# v0_4_0.net
KiCad netlist of a schematic drawn in EAGLE
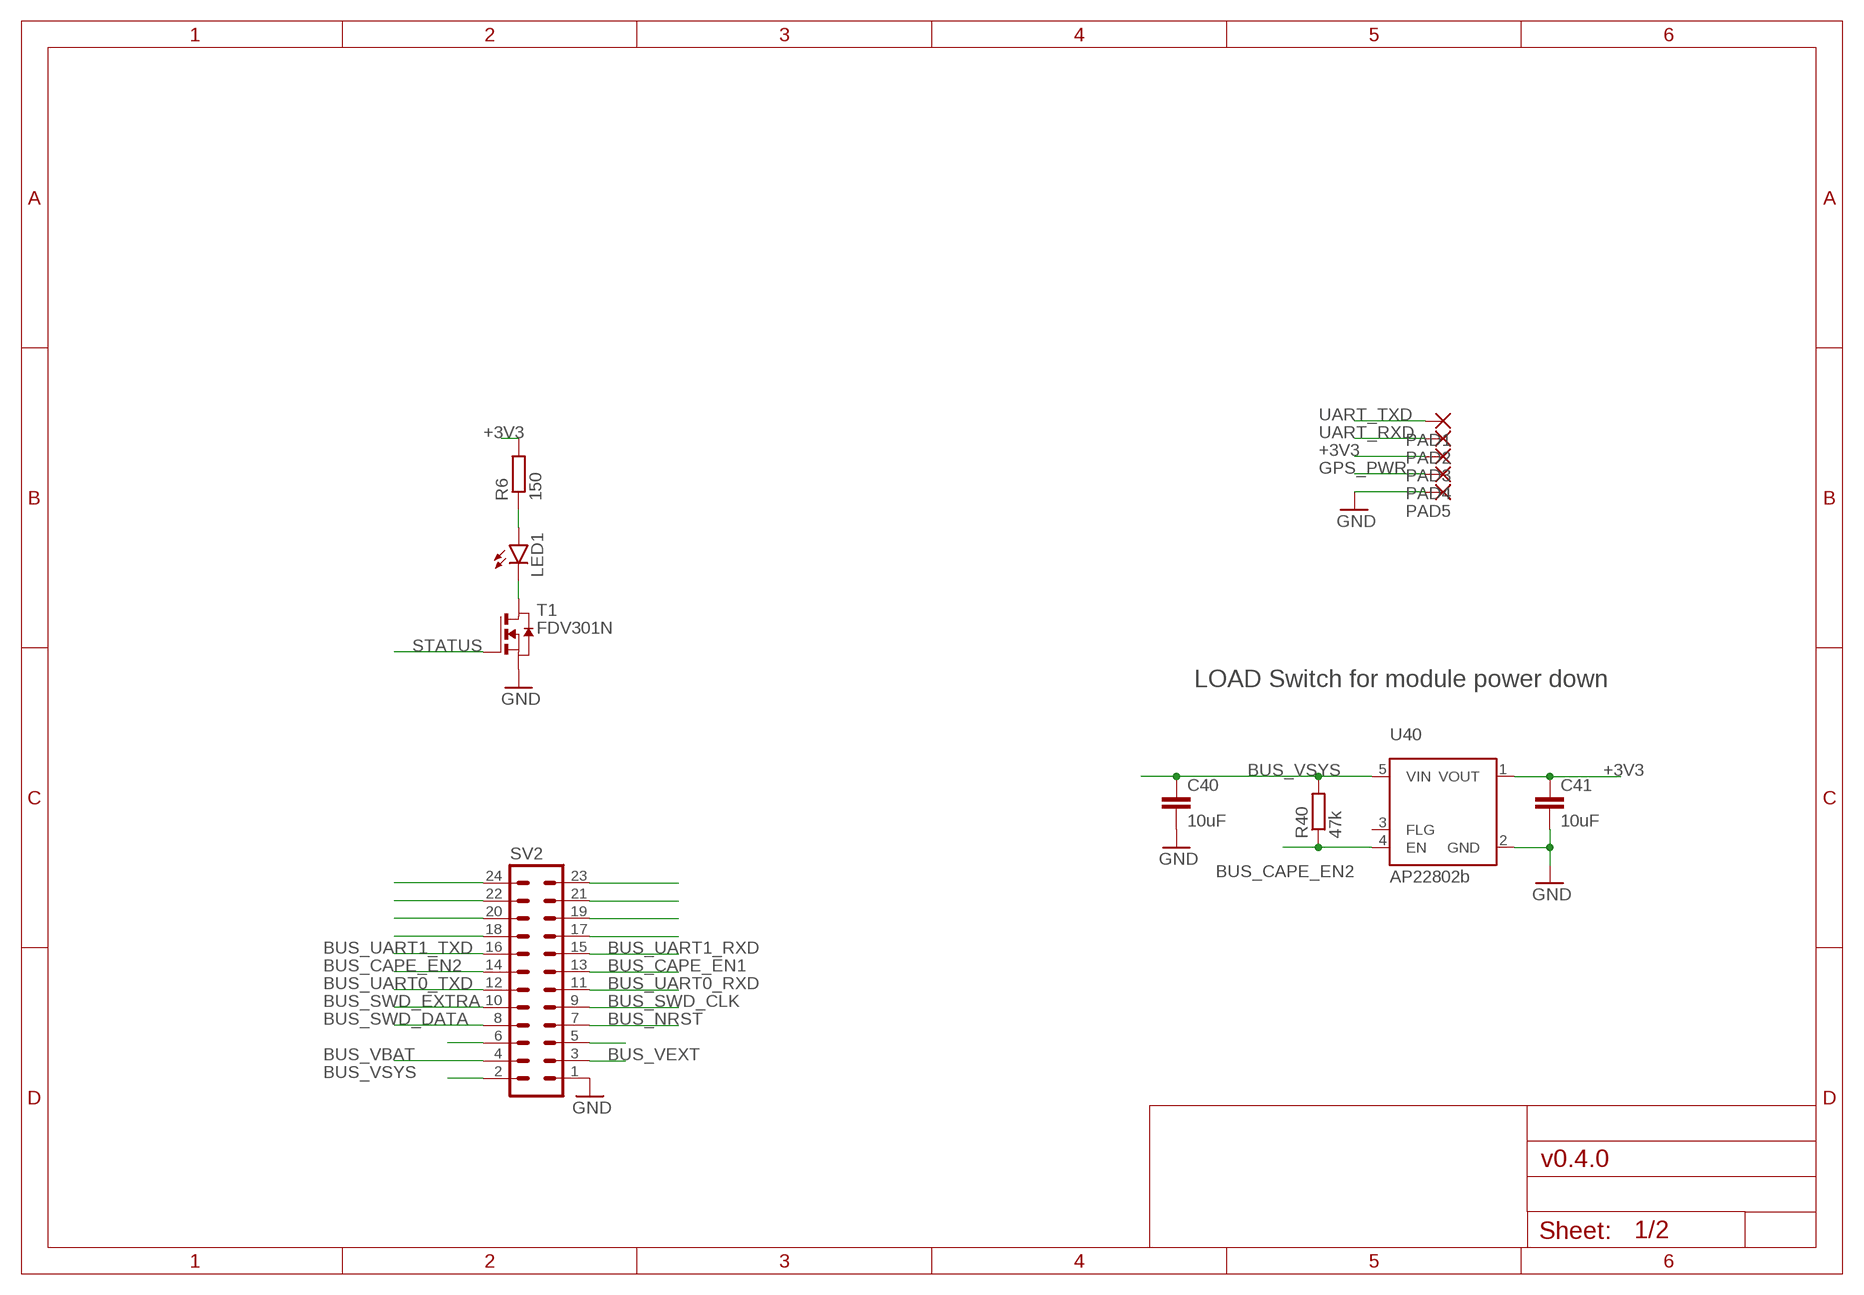
[diagram p0: schematic, sheet 1]
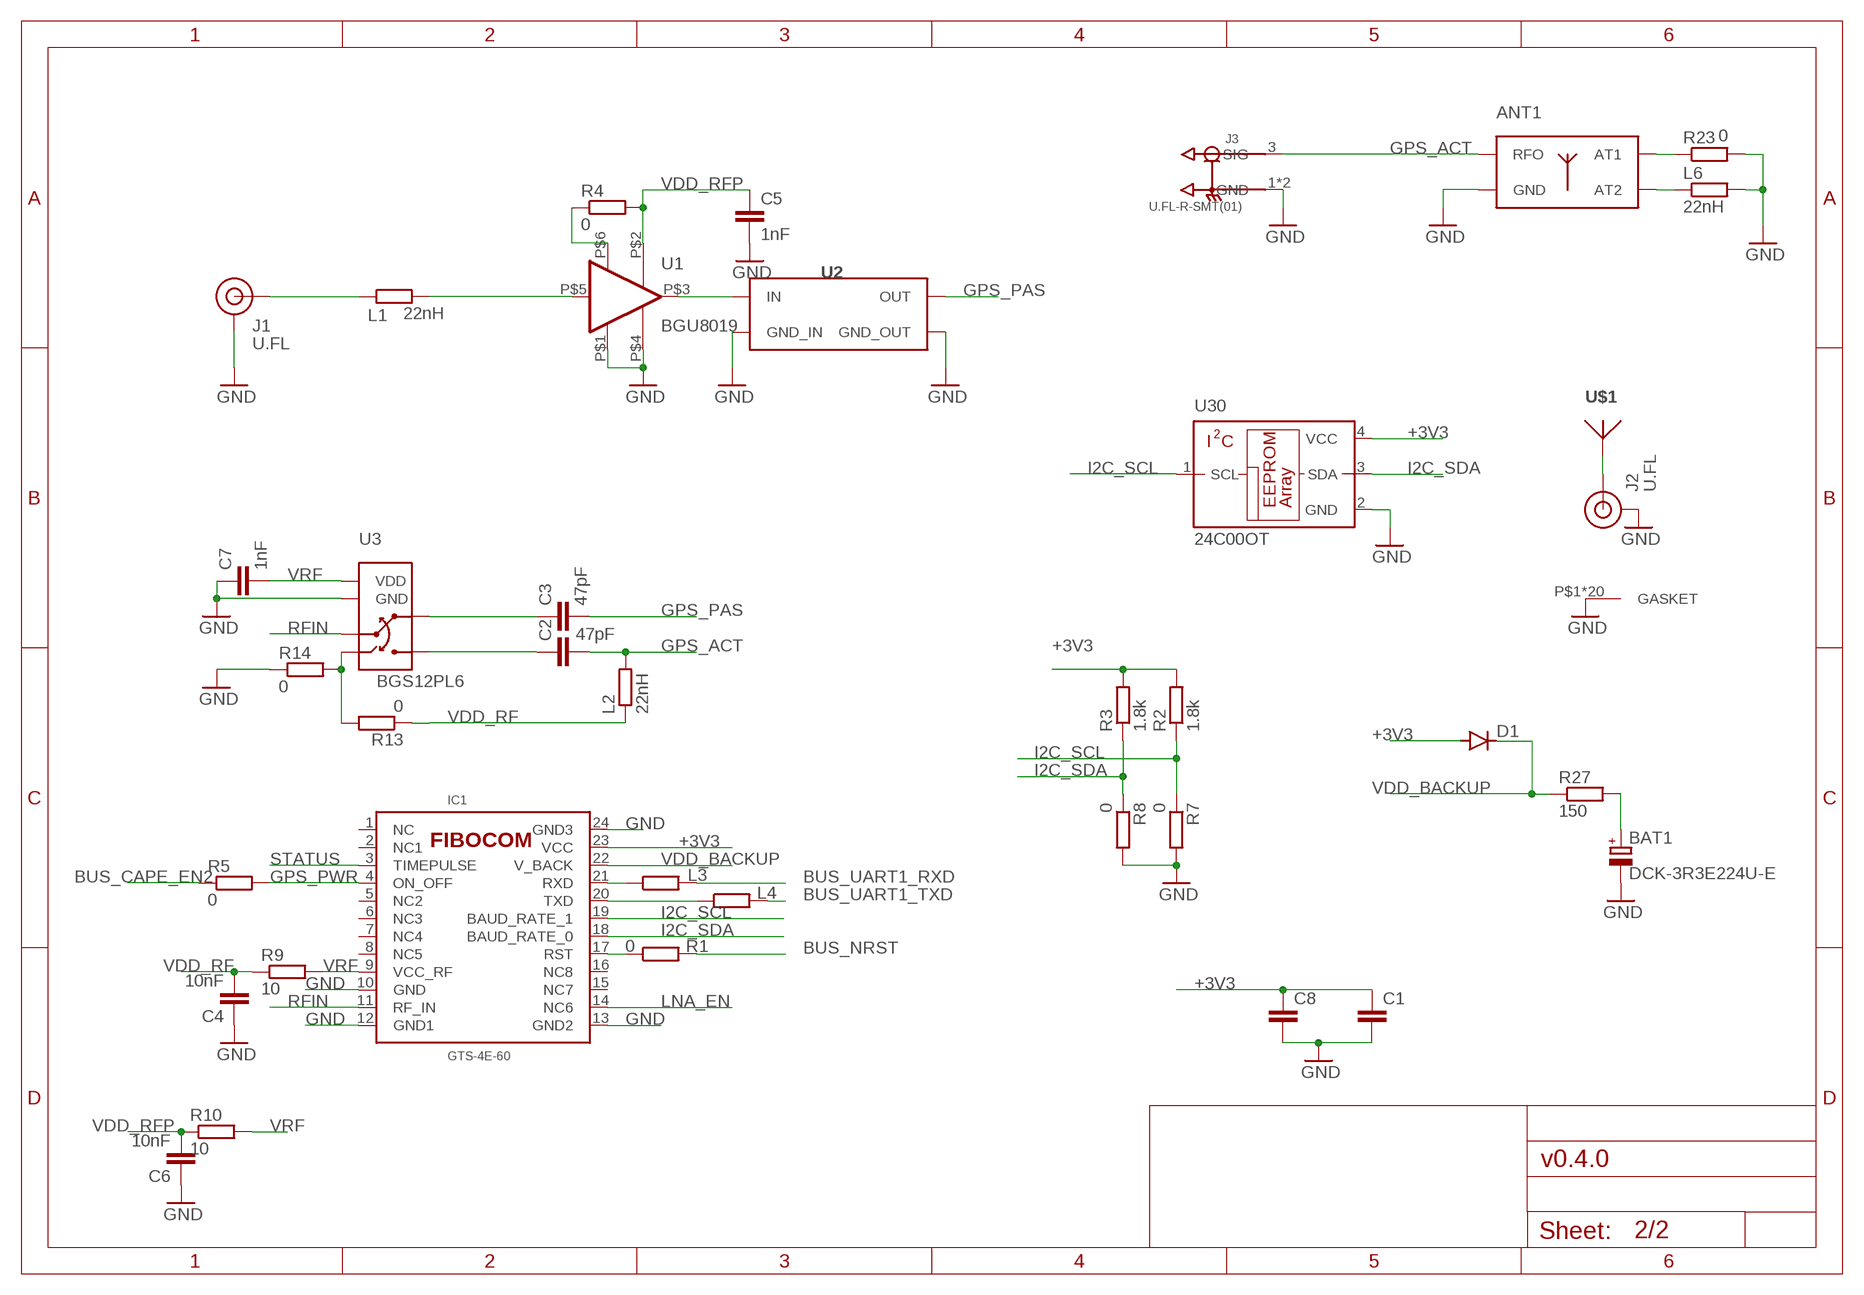
[diagram p1: schematic, sheet 2]

(export (version "E")
  (design (tool "Eeschema 10.0.6"))
  (components
    (comp (ref "ANT1")
      (value "M20047")
      (footprint "eagle-import:PCBCOMPONENT_1")
      (libsource (lib "eagle-import") (part "M20047"))
    )
    (comp (ref "BAT1")
      (value "DCK-3R3E224U-E")
      (footprint "eagle-import:621")
      (libsource (lib "eagle-import") (part "DCK-3R3E224U-E"))
    )
    (comp (ref "C1")
      (value "C-EUC0603")
      (footprint "eagle-import:C0603")
      (libsource (lib "eagle-import") (part "C-EUC0603"))
    )
    (comp (ref "C2")
      (value "47pF")
      (footprint "eagle-import:C0402")
      (libsource (lib "eagle-import") (part "C-EUC0402"))
    )
    (comp (ref "C3")
      (value "47pF")
      (footprint "eagle-import:C0402")
      (libsource (lib "eagle-import") (part "C-EUC0402"))
    )
    (comp (ref "C4")
      (value "10nF")
      (footprint "eagle-import:C0402")
      (libsource (lib "eagle-import") (part "C-EUC0402"))
    )
    (comp (ref "C5")
      (value "1nF")
      (footprint "eagle-import:C0402")
      (libsource (lib "eagle-import") (part "C-EUC0402"))
    )
    (comp (ref "C6")
      (value "10nF")
      (footprint "eagle-import:C0402")
      (libsource (lib "eagle-import") (part "C-EUC0402"))
    )
    (comp (ref "C7")
      (value "1nF")
      (footprint "eagle-import:C0402")
      (libsource (lib "eagle-import") (part "C-EUC0402"))
    )
    (comp (ref "C8")
      (value "C-EUC0402")
      (footprint "eagle-import:C0402")
      (libsource (lib "eagle-import") (part "C-EUC0402"))
    )
    (comp (ref "D1")
      (value "DIODE-SOD323-R")
      (footprint "eagle-import:SOD323-R")
      (libsource (lib "eagle-import") (part "DIODE-SOD323-R"))
    )
    (comp (ref "IC1")
      (value "GTS-4E-60")
      (footprint "eagle-import:_GTS_4E_60")
      (libsource (lib "eagle-import") (part "GTS-4E-60"))
    )
    (comp (ref "J1")
      (value "U.FL")
      (footprint "eagle-import:U.FL")
      (libsource (lib "eagle-import") (part "U.FL2PIN"))
    )
    (comp (ref "J2")
      (value "U.FL")
      (footprint "eagle-import:U.FL")
      (libsource (lib "eagle-import") (part "U.FL2PIN"))
    )
    (comp (ref "J3")
      (value "U.FL-R-SMT(01)")
      (footprint "eagle-import:HRS_U.FL-R-SMT(01)")
      (fields (field (name "MF") "Hirose") (field (name "MP") "U.FL-R-SMT_01_"))
      (libsource (lib "eagle-import") (part "U.FL-R-SMT(01)"))
    )
    (comp (ref "L1")
      (value "22nH")
      (footprint "eagle-import:R0402")
      (libsource (lib "eagle-import") (part "R-EU_R0402"))
    )
    (comp (ref "L2")
      (value "22nH")
      (footprint "eagle-import:R0402")
      (libsource (lib "eagle-import") (part "R-EU_R0402"))
    )
    (comp (ref "L3")
      (value "R-EU_R0402")
      (footprint "eagle-import:R0402")
      (libsource (lib "eagle-import") (part "R-EU_R0402"))
    )
    (comp (ref "L4")
      (value "R-EU_R0402")
      (footprint "eagle-import:R0402")
      (libsource (lib "eagle-import") (part "R-EU_R0402"))
    )
    (comp (ref "L6")
      (value "22nH")
      (footprint "eagle-import:R0402")
      (libsource (lib "eagle-import") (part "R-EU_R0402"))
    )
    (comp (ref "R1")
      (value "0")
      (footprint "eagle-import:R0402")
      (libsource (lib "eagle-import") (part "R-EU_R0402"))
    )
    (comp (ref "R2")
      (value "1.8k")
      (footprint "eagle-import:R0402")
      (libsource (lib "eagle-import") (part "R-EU_R0402"))
    )
    (comp (ref "R3")
      (value "1.8k")
      (footprint "eagle-import:R0402")
      (libsource (lib "eagle-import") (part "R-EU_R0402"))
    )
    (comp (ref "R4")
      (value "0")
      (footprint "eagle-import:R0402")
      (libsource (lib "eagle-import") (part "R-EU_R0402"))
    )
    (comp (ref "R5")
      (value "0")
      (footprint "eagle-import:R0402")
      (libsource (lib "eagle-import") (part "R-EU_R0402"))
    )
    (comp (ref "R7")
      (value "0")
      (footprint "eagle-import:R0402")
      (libsource (lib "eagle-import") (part "R-EU_R0402"))
    )
    (comp (ref "R8")
      (value "0")
      (footprint "eagle-import:R0402")
      (libsource (lib "eagle-import") (part "R-EU_R0402"))
    )
    (comp (ref "R9")
      (value "10")
      (footprint "eagle-import:R0402")
      (libsource (lib "eagle-import") (part "R-EU_R0402"))
    )
    (comp (ref "R10")
      (value "10")
      (footprint "eagle-import:R0402")
      (libsource (lib "eagle-import") (part "R-EU_R0402"))
    )
    (comp (ref "R13")
      (value "0")
      (footprint "eagle-import:R0402")
      (libsource (lib "eagle-import") (part "R-EU_R0402"))
    )
    (comp (ref "R14")
      (value "0")
      (footprint "eagle-import:R0402")
      (libsource (lib "eagle-import") (part "R-EU_R0402"))
    )
    (comp (ref "R23")
      (value "0")
      (footprint "eagle-import:R0402")
      (libsource (lib "eagle-import") (part "R-EU_R0402"))
    )
    (comp (ref "R27")
      (value "150")
      (footprint "eagle-import:R0402")
      (libsource (lib "eagle-import") (part "R-EU_R0402"))
    )
    (comp (ref "U$1")
      (value "ANT1590-2540A")
      (footprint "eagle-import:2540A")
      (libsource (lib "eagle-import") (part "ANT1590-2540A"))
    )
    (comp (ref "U$2")
      (value "2118718-2")
      (footprint "eagle-import:2118717-2")
      (libsource (lib "eagle-import") (part "2118718-2"))
    )
    (comp (ref "U1")
      (value "BGU8019")
      (footprint "eagle-import:XSON6")
      (libsource (lib "eagle-import") (part "BGU8019"))
    )
    (comp (ref "U2")
      (value "B3916B8813P810")
      (footprint "eagle-import:XSON5")
      (libsource (lib "eagle-import") (part "B3916B8813P810"))
    )
    (comp (ref "U3")
      (value "BGS12PL6")
      (footprint "eagle-import:TSLP-6-4")
      (libsource (lib "eagle-import") (part "BGS12PL6"))
    )
    (comp (ref "U30")
      (value "24C00OT")
      (footprint "eagle-import:SOT23-5L")
      (fields (field (name "MF") "MICROCHIP") (field (name "MPN") "24C00T-I/OT"))
      (libsource (lib "eagle-import") (part "2400OTC"))
    )
    (comp (ref "C40")
      (value "10uF")
      (footprint "eagle-import:C0603")
      (libsource (lib "eagle-import") (part "C-EUC0603"))
    )
    (comp (ref "C41")
      (value "10uF")
      (footprint "eagle-import:C0603")
      (libsource (lib "eagle-import") (part "C-EUC0603"))
    )
    (comp (ref "LED1")
      (value "LEDCHIP-LED0603")
      (footprint "eagle-import:CHIP-LED0603")
      (libsource (lib "eagle-import") (part "LEDCHIP-LED0603"))
    )
    (comp (ref "PAD1")
      (value "1,6/0,9")
      (footprint "eagle-import:1,6_0,9")
      (libsource (lib "eagle-import") (part "1,6/0,9"))
    )
    (comp (ref "PAD2")
      (value "1,6/0,9")
      (footprint "eagle-import:1,6_0,9")
      (libsource (lib "eagle-import") (part "1,6/0,9"))
    )
    (comp (ref "PAD3")
      (value "1,6/0,9")
      (footprint "eagle-import:1,6_0,9")
      (libsource (lib "eagle-import") (part "1,6/0,9"))
    )
    (comp (ref "PAD4")
      (value "1,6/0,9")
      (footprint "eagle-import:1,6_0,9")
      (libsource (lib "eagle-import") (part "1,6/0,9"))
    )
    (comp (ref "PAD5")
      (value "1,6/0,9")
      (footprint "eagle-import:1,6_0,9")
      (libsource (lib "eagle-import") (part "1,6/0,9"))
    )
    (comp (ref "R6")
      (value "150")
      (footprint "eagle-import:R0402")
      (libsource (lib "eagle-import") (part "R-EU_R0402"))
    )
    (comp (ref "R40")
      (value "47k")
      (footprint "eagle-import:R0402")
      (libsource (lib "eagle-import") (part "R-EU_R0402"))
    )
    (comp (ref "SV2")
      (value "MA12-2")
      (footprint "eagle-import:MA12-2")
      (libsource (lib "eagle-import") (part "MA12-2"))
    )
    (comp (ref "T1")
      (value "FDV301N")
      (footprint "eagle-import:SOT-23")
      (libsource (lib "eagle-import") (part "NMOSSOT23"))
    )
    (comp (ref "U40")
      (value "AP22802b")
      (footprint "eagle-import:SOT25")
      (libsource (lib "eagle-import") (part "AP22802"))
    )
  )
  (nets
    (net (code "1") (name "+3V3") (class "Default")
      (node (ref "C1") (pin "1") (pinfunction "1_1") (pintype "passive"))
      (node (ref "C41") (pin "1") (pinfunction "1_1") (pintype "passive"))
      (node (ref "C8") (pin "1") (pinfunction "1_1") (pintype "passive"))
      (node (ref "D1") (pin "A") (pinfunction "A_A") (pintype "passive"))
      (node (ref "IC1") (pin "23") (pinfunction "VCC_23") (pintype "bidirectional"))
      (node (ref "PAD3") (pin "1") (pinfunction "P_1") (pintype "passive"))
      (node (ref "R2") (pin "2") (pinfunction "2_2") (pintype "passive"))
      (node (ref "R3") (pin "2") (pinfunction "2_2") (pintype "passive"))
      (node (ref "R6") (pin "2") (pinfunction "2_2") (pintype "passive"))
      (node (ref "U30") (pin "4") (pinfunction "VCC_4") (pintype "power_in"))
      (node (ref "U40") (pin "1") (pinfunction "VOUT_1") (pintype "bidirectional"))
    )
    (net (code "2") (name "BUS_CAPE_EN1") (class "Default")
      (node (ref "SV2") (pin "13") (pinfunction "13_13") (pintype "passive"))
    )
    (net (code "3") (name "BUS_CAPE_EN2") (class "Default")
      (node (ref "R40") (pin "1") (pinfunction "1_1") (pintype "passive"))
      (node (ref "R5") (pin "1") (pinfunction "1_1") (pintype "passive"))
      (node (ref "SV2") (pin "14") (pinfunction "14_14") (pintype "passive"))
      (node (ref "U40") (pin "4") (pinfunction "EN_4") (pintype "bidirectional"))
    )
    (net (code "4") (name "BUS_NRST") (class "Default")
      (node (ref "R1") (pin "2") (pinfunction "2_2") (pintype "passive"))
      (node (ref "SV2") (pin "7") (pinfunction "7_7") (pintype "passive"))
    )
    (net (code "5") (name "BUS_SWD_CLK") (class "Default")
      (node (ref "SV2") (pin "9") (pinfunction "9_9") (pintype "passive"))
    )
    (net (code "6") (name "BUS_SWD_DATA") (class "Default")
      (node (ref "SV2") (pin "8") (pinfunction "8_8") (pintype "passive"))
    )
    (net (code "7") (name "BUS_SWD_EXTRA") (class "Default")
      (node (ref "SV2") (pin "10") (pinfunction "10_10") (pintype "passive"))
    )
    (net (code "8") (name "BUS_UART0_RXD") (class "Default")
      (node (ref "SV2") (pin "11") (pinfunction "11_11") (pintype "passive"))
    )
    (net (code "9") (name "BUS_UART0_TXD") (class "Default")
      (node (ref "SV2") (pin "12") (pinfunction "12_12") (pintype "passive"))
    )
    (net (code "10") (name "BUS_UART1_RXD") (class "Default")
      (node (ref "L3") (pin "2") (pinfunction "2_2") (pintype "passive"))
      (node (ref "SV2") (pin "15") (pinfunction "15_15") (pintype "passive"))
    )
    (net (code "11") (name "BUS_UART1_TXD") (class "Default")
      (node (ref "L4") (pin "2") (pinfunction "2_2") (pintype "passive"))
      (node (ref "SV2") (pin "16") (pinfunction "16_16") (pintype "passive"))
    )
    (net (code "12") (name "BUS_VBAT") (class "Default")
      (node (ref "SV2") (pin "4") (pinfunction "4_4") (pintype "passive"))
    )
    (net (code "13") (name "BUS_VEXT") (class "Default")
      (node (ref "SV2") (pin "3") (pinfunction "3_3") (pintype "passive"))
    )
    (net (code "14") (name "BUS_VSYS") (class "Default")
      (node (ref "C40") (pin "1") (pinfunction "1_1") (pintype "passive"))
      (node (ref "R40") (pin "2") (pinfunction "2_2") (pintype "passive"))
      (node (ref "SV2") (pin "2") (pinfunction "2_2") (pintype "passive"))
      (node (ref "U40") (pin "5") (pinfunction "VIN_5") (pintype "bidirectional"))
    )
    (net (code "15") (name "GND") (class "Default")
      (node (ref "ANT1") (pin "2") (pinfunction "GND_2") (pintype "power_in"))
      (node (ref "ANT1") (pin "3") (pinfunction "GND_3") (pintype "power_in"))
      (node (ref "ANT1") (pin "4") (pinfunction "GND_4") (pintype "power_in"))
      (node (ref "BAT1") (pin "-") (pinfunction "-_-") (pintype "passive"))
      (node (ref "C1") (pin "2") (pinfunction "2_2") (pintype "passive"))
      (node (ref "C4") (pin "1") (pinfunction "1_1") (pintype "passive"))
      (node (ref "C40") (pin "2") (pinfunction "2_2") (pintype "passive"))
      (node (ref "C41") (pin "2") (pinfunction "2_2") (pintype "passive"))
      (node (ref "C5") (pin "2") (pinfunction "2_2") (pintype "passive"))
      (node (ref "C6") (pin "1") (pinfunction "1_1") (pintype "passive"))
      (node (ref "C7") (pin "1") (pinfunction "1_1") (pintype "passive"))
      (node (ref "C8") (pin "2") (pinfunction "2_2") (pintype "passive"))
      (node (ref "IC1") (pin "10") (pinfunction "GND_10") (pintype "bidirectional"))
      (node (ref "IC1") (pin "12") (pinfunction "GND1_12") (pintype "bidirectional"))
      (node (ref "IC1") (pin "13") (pinfunction "GND2_13") (pintype "bidirectional"))
      (node (ref "IC1") (pin "24") (pinfunction "GND3_24") (pintype "bidirectional"))
      (node (ref "J1") (pin "1") (pinfunction "GND_1") (pintype "bidirectional"))
      (node (ref "J1") (pin "2") (pinfunction "GND_2") (pintype "bidirectional"))
      (node (ref "J2") (pin "1") (pinfunction "GND_1") (pintype "bidirectional"))
      (node (ref "J2") (pin "2") (pinfunction "GND_2") (pintype "bidirectional"))
      (node (ref "J3") (pin "1") (pinfunction "GND_1") (pintype "passive"))
      (node (ref "J3") (pin "2") (pinfunction "GND_2") (pintype "passive"))
      (node (ref "L6") (pin "2") (pinfunction "2_2") (pintype "passive"))
      (node (ref "PAD5") (pin "1") (pinfunction "P_1") (pintype "passive"))
      (node (ref "R14") (pin "1") (pinfunction "1_1") (pintype "passive"))
      (node (ref "R23") (pin "2") (pinfunction "2_2") (pintype "passive"))
      (node (ref "R7") (pin "2") (pinfunction "2_2") (pintype "passive"))
      (node (ref "R8") (pin "2") (pinfunction "2_2") (pintype "passive"))
      (node (ref "SV2") (pin "1") (pinfunction "1_1") (pintype "passive"))
      (node (ref "T1") (pin "2") (pinfunction "S_2") (pintype "passive"))
      (node (ref "U$2") (pin "P$1") (pinfunction "GASKET_P$1") (pintype "bidirectional"))
      (node (ref "U$2") (pin "P$10") (pinfunction "GASKET_P$10") (pintype "bidirectional"))
      (node (ref "U$2") (pin "P$11") (pinfunction "GASKET_P$11") (pintype "bidirectional"))
      (node (ref "U$2") (pin "P$12") (pinfunction "GASKET_P$12") (pintype "bidirectional"))
      (node (ref "U$2") (pin "P$13") (pinfunction "GASKET_P$13") (pintype "bidirectional"))
      (node (ref "U$2") (pin "P$14") (pinfunction "GASKET_P$14") (pintype "bidirectional"))
      (node (ref "U$2") (pin "P$15") (pinfunction "GASKET_P$15") (pintype "bidirectional"))
      (node (ref "U$2") (pin "P$16") (pinfunction "GASKET_P$16") (pintype "bidirectional"))
      (node (ref "U$2") (pin "P$17") (pinfunction "GASKET_P$17") (pintype "bidirectional"))
      (node (ref "U$2") (pin "P$18") (pinfunction "GASKET_P$18") (pintype "bidirectional"))
      (node (ref "U$2") (pin "P$19") (pinfunction "GASKET_P$19") (pintype "bidirectional"))
      (node (ref "U$2") (pin "P$2") (pinfunction "GASKET_P$2") (pintype "bidirectional"))
      (node (ref "U$2") (pin "P$20") (pinfunction "GASKET_P$20") (pintype "bidirectional"))
      (node (ref "U$2") (pin "P$3") (pinfunction "GASKET_P$3") (pintype "bidirectional"))
      (node (ref "U$2") (pin "P$4") (pinfunction "GASKET_P$4") (pintype "bidirectional"))
      (node (ref "U$2") (pin "P$5") (pinfunction "GASKET_P$5") (pintype "bidirectional"))
      (node (ref "U$2") (pin "P$6") (pinfunction "GASKET_P$6") (pintype "bidirectional"))
      (node (ref "U$2") (pin "P$7") (pinfunction "GASKET_P$7") (pintype "bidirectional"))
      (node (ref "U$2") (pin "P$8") (pinfunction "GASKET_P$8") (pintype "bidirectional"))
      (node (ref "U$2") (pin "P$9") (pinfunction "GASKET_P$9") (pintype "bidirectional"))
      (node (ref "U1") (pin "P$1") (pinfunction "GND_P$1") (pintype "power_in"))
      (node (ref "U1") (pin "P$4") (pinfunction "GND_RF_P$4") (pintype "passive"))
      (node (ref "U2") (pin "2") (pinfunction "GND_IN_2") (pintype "bidirectional"))
      (node (ref "U2") (pin "3") (pinfunction "GND_OUT_3") (pintype "bidirectional"))
      (node (ref "U2") (pin "5") (pinfunction "GND_IN_5") (pintype "bidirectional"))
      (node (ref "U3") (pin "P$2") (pinfunction "GND_P$2") (pintype "power_in"))
      (node (ref "U30") (pin "2") (pinfunction "GND_2") (pintype "power_in"))
      (node (ref "U40") (pin "2") (pinfunction "GND_2") (pintype "bidirectional"))
    )
    (net (code "16") (name "GPS_ACT") (class "Default")
      (node (ref "ANT1") (pin "5") (pinfunction "RFO_5") (pintype "input"))
      (node (ref "C2") (pin "2") (pinfunction "2_2") (pintype "passive"))
      (node (ref "J3") (pin "3") (pinfunction "SIG_3") (pintype "passive"))
      (node (ref "L2") (pin "2") (pinfunction "2_2") (pintype "passive"))
    )
    (net (code "17") (name "GPS_PAS") (class "Default")
      (node (ref "C3") (pin "2") (pinfunction "2_2") (pintype "passive"))
      (node (ref "U2") (pin "4") (pinfunction "OUT_4") (pintype "bidirectional"))
    )
    (net (code "18") (name "GPS_PWR") (class "Default")
      (node (ref "IC1") (pin "4") (pinfunction "ON_OFF_4") (pintype "bidirectional"))
      (node (ref "PAD4") (pin "1") (pinfunction "P_1") (pintype "passive"))
      (node (ref "R5") (pin "2") (pinfunction "2_2") (pintype "passive"))
    )
    (net (code "19") (name "I2C_SCL") (class "Default")
      (node (ref "IC1") (pin "19") (pinfunction "BAUD_RATE_1_19") (pintype "bidirectional"))
      (node (ref "R2") (pin "1") (pinfunction "1_1") (pintype "passive"))
      (node (ref "R7") (pin "1") (pinfunction "1_1") (pintype "passive"))
      (node (ref "U30") (pin "1") (pinfunction "SCL_1") (pintype "input"))
    )
    (net (code "20") (name "I2C_SDA") (class "Default")
      (node (ref "IC1") (pin "18") (pinfunction "BAUD_RATE_0_18") (pintype "bidirectional"))
      (node (ref "R3") (pin "1") (pinfunction "1_1") (pintype "passive"))
      (node (ref "R8") (pin "1") (pinfunction "1_1") (pintype "passive"))
      (node (ref "U30") (pin "3") (pinfunction "SDA_3") (pintype "bidirectional"))
    )
    (net (code "21") (name "LNA_EN") (class "Default")
      (node (ref "IC1") (pin "14") (pinfunction "NC6_14") (pintype "bidirectional"))
    )
    (net (code "22") (name "Net-(ANT1-AT1)") (class "Default")
      (node (ref "ANT1") (pin "1") (pinfunction "AT1_1") (pintype "bidirectional"))
      (node (ref "R23") (pin "1") (pinfunction "1_1") (pintype "passive"))
    )
    (net (code "23") (name "Net-(ANT1-AT2)") (class "Default")
      (node (ref "ANT1") (pin "6") (pinfunction "AT2_6") (pintype "bidirectional"))
      (node (ref "L6") (pin "1") (pinfunction "1_1") (pintype "passive"))
    )
    (net (code "24") (name "Net-(BAT1-Pad+)") (class "Default")
      (node (ref "BAT1") (pin "+") (pinfunction "+_+") (pintype "passive"))
      (node (ref "R27") (pin "2") (pinfunction "2_2") (pintype "passive"))
    )
    (net (code "25") (name "Net-(IC1-RST)") (class "Default")
      (node (ref "IC1") (pin "17") (pinfunction "RST_17") (pintype "bidirectional"))
      (node (ref "R1") (pin "1") (pinfunction "1_1") (pintype "passive"))
    )
    (net (code "26") (name "Net-(J1-SIGNAL)") (class "Default")
      (node (ref "J1") (pin "FEED") (pinfunction "SIGNAL_FEED") (pintype "bidirectional"))
      (node (ref "L1") (pin "1") (pinfunction "1_1") (pintype "passive"))
    )
    (net (code "27") (name "Net-(J2-SIGNAL)") (class "Default")
      (node (ref "J2") (pin "FEED") (pinfunction "SIGNAL_FEED") (pintype "bidirectional"))
      (node (ref "U$1") (pin "P$1") (pinfunction "P$1_P$1") (pintype "bidirectional"))
    )
    (net (code "28") (name "Net-(LED1-PadA)") (class "Default")
      (node (ref "LED1") (pin "A") (pinfunction "A_A") (pintype "passive"))
      (node (ref "R6") (pin "1") (pinfunction "1_1") (pintype "passive"))
    )
    (net (code "29") (name "Net-(T1-D)") (class "Default")
      (node (ref "LED1") (pin "C") (pinfunction "C_C") (pintype "passive"))
      (node (ref "T1") (pin "1") (pinfunction "D_1") (pintype "passive"))
    )
    (net (code "30") (name "Net-(U1-ENABLE)") (class "Default")
      (node (ref "R4") (pin "1") (pinfunction "1_1") (pintype "passive"))
      (node (ref "U1") (pin "P$6") (pinfunction "ENABLE_P$6") (pintype "power_in"))
    )
    (net (code "31") (name "Net-(U1-RF_IN)") (class "Default")
      (node (ref "L1") (pin "2") (pinfunction "2_2") (pintype "passive"))
      (node (ref "U1") (pin "P$5") (pinfunction "RF_IN_P$5") (pintype "input"))
    )
    (net (code "32") (name "Net-(U1-RF_OUT)") (class "Default")
      (node (ref "U1") (pin "P$3") (pinfunction "RF_OUT_P$3") (pintype "output"))
      (node (ref "U2") (pin "1") (pinfunction "IN_1") (pintype "bidirectional"))
    )
    (net (code "33") (name "Net-(U3-P$4)") (class "Default")
      (node (ref "R13") (pin "2") (pinfunction "2_2") (pintype "passive"))
      (node (ref "R14") (pin "2") (pinfunction "2_2") (pintype "passive"))
      (node (ref "U3") (pin "P$6") (pinfunction "P$4_P$6") (pintype "bidirectional"))
    )
    (net (code "34") (name "Net-(U3-RF1)") (class "Default")
      (node (ref "C3") (pin "1") (pinfunction "1_1") (pintype "passive"))
      (node (ref "U3") (pin "P$3") (pinfunction "RF1_P$3") (pintype "bidirectional"))
    )
    (net (code "35") (name "Net-(U3-RF2)") (class "Default")
      (node (ref "C2") (pin "1") (pinfunction "1_1") (pintype "passive"))
      (node (ref "U3") (pin "P$1") (pinfunction "RF2_P$1") (pintype "bidirectional"))
    )
    (net (code "36") (name "RFIN") (class "Default")
      (node (ref "IC1") (pin "11") (pinfunction "RF_IN_11") (pintype "bidirectional"))
      (node (ref "U3") (pin "P$5") (pinfunction "RFIN_P$5") (pintype "bidirectional"))
    )
    (net (code "37") (name "STATUS") (class "Default")
      (node (ref "IC1") (pin "3") (pinfunction "TIMEPULSE_3") (pintype "bidirectional"))
      (node (ref "T1") (pin "3") (pinfunction "G_3") (pintype "passive"))
    )
    (net (code "38") (name "UART_RXD") (class "Default")
      (node (ref "IC1") (pin "20") (pinfunction "TXD_20") (pintype "bidirectional"))
      (node (ref "L4") (pin "1") (pinfunction "1_1") (pintype "passive"))
      (node (ref "PAD2") (pin "1") (pinfunction "P_1") (pintype "passive"))
    )
    (net (code "39") (name "UART_TXD") (class "Default")
      (node (ref "IC1") (pin "21") (pinfunction "RXD_21") (pintype "bidirectional"))
      (node (ref "L3") (pin "1") (pinfunction "1_1") (pintype "passive"))
      (node (ref "PAD1") (pin "1") (pinfunction "P_1") (pintype "passive"))
    )
    (net (code "40") (name "VDD_BACKUP") (class "Default")
      (node (ref "D1") (pin "C") (pinfunction "C_C") (pintype "passive"))
      (node (ref "IC1") (pin "22") (pinfunction "V_BACK_22") (pintype "bidirectional"))
      (node (ref "R27") (pin "1") (pinfunction "1_1") (pintype "passive"))
    )
    (net (code "41") (name "VDD_RF") (class "Default")
      (node (ref "C4") (pin "2") (pinfunction "2_2") (pintype "passive"))
      (node (ref "L2") (pin "1") (pinfunction "1_1") (pintype "passive"))
      (node (ref "R13") (pin "1") (pinfunction "1_1") (pintype "passive"))
      (node (ref "R9") (pin "1") (pinfunction "1_1") (pintype "passive"))
    )
    (net (code "42") (name "VDD_RFP") (class "Default")
      (node (ref "C5") (pin "1") (pinfunction "1_1") (pintype "passive"))
      (node (ref "C6") (pin "2") (pinfunction "2_2") (pintype "passive"))
      (node (ref "R10") (pin "1") (pinfunction "1_1") (pintype "passive"))
      (node (ref "R4") (pin "2") (pinfunction "2_2") (pintype "passive"))
      (node (ref "U1") (pin "P$2") (pinfunction "VCC_P$2") (pintype "passive"))
    )
    (net (code "43") (name "VRF") (class "Default")
      (node (ref "C7") (pin "2") (pinfunction "2_2") (pintype "passive"))
      (node (ref "IC1") (pin "9") (pinfunction "VCC_RF_9") (pintype "bidirectional"))
      (node (ref "R10") (pin "2") (pinfunction "2_2") (pintype "passive"))
      (node (ref "R9") (pin "2") (pinfunction "2_2") (pintype "passive"))
      (node (ref "U3") (pin "P$4") (pinfunction "VDD_P$4") (pintype "power_in"))
    )
    (net (code "44") (name "unconnected-(IC1-NC-Pad1)") (class "Default")
      (node (ref "IC1") (pin "1") (pinfunction "NC_1") (pintype "bidirectional"))
    )
    (net (code "45") (name "unconnected-(IC1-NC1-Pad2)") (class "Default")
      (node (ref "IC1") (pin "2") (pinfunction "NC1_2") (pintype "bidirectional"))
    )
    (net (code "46") (name "unconnected-(IC1-NC2-Pad5)") (class "Default")
      (node (ref "IC1") (pin "5") (pinfunction "NC2_5") (pintype "bidirectional"))
    )
    (net (code "47") (name "unconnected-(IC1-NC3-Pad6)") (class "Default")
      (node (ref "IC1") (pin "6") (pinfunction "NC3_6") (pintype "bidirectional"))
    )
    (net (code "48") (name "unconnected-(IC1-NC4-Pad7)") (class "Default")
      (node (ref "IC1") (pin "7") (pinfunction "NC4_7") (pintype "bidirectional"))
    )
    (net (code "49") (name "unconnected-(IC1-NC5-Pad8)") (class "Default")
      (node (ref "IC1") (pin "8") (pinfunction "NC5_8") (pintype "bidirectional"))
    )
    (net (code "50") (name "unconnected-(IC1-NC7-Pad15)") (class "Default")
      (node (ref "IC1") (pin "15") (pinfunction "NC7_15") (pintype "bidirectional"))
    )
    (net (code "51") (name "unconnected-(IC1-NC8-Pad16)") (class "Default")
      (node (ref "IC1") (pin "16") (pinfunction "NC8_16") (pintype "bidirectional"))
    )
    (net (code "52") (name "unconnected-(SV2-Pad5)") (class "Default")
      (node (ref "SV2") (pin "5") (pinfunction "5_5") (pintype "passive"))
    )
    (net (code "53") (name "unconnected-(SV2-Pad6)") (class "Default")
      (node (ref "SV2") (pin "6") (pinfunction "6_6") (pintype "passive"))
    )
    (net (code "54") (name "unconnected-(SV2-Pad17)") (class "Default")
      (node (ref "SV2") (pin "17") (pinfunction "17_17") (pintype "passive"))
    )
    (net (code "55") (name "unconnected-(SV2-Pad18)") (class "Default")
      (node (ref "SV2") (pin "18") (pinfunction "18_18") (pintype "passive"))
    )
    (net (code "56") (name "unconnected-(SV2-Pad19)") (class "Default")
      (node (ref "SV2") (pin "19") (pinfunction "19_19") (pintype "passive"))
    )
    (net (code "57") (name "unconnected-(SV2-Pad20)") (class "Default")
      (node (ref "SV2") (pin "20") (pinfunction "20_20") (pintype "passive"))
    )
    (net (code "58") (name "unconnected-(SV2-Pad21)") (class "Default")
      (node (ref "SV2") (pin "21") (pinfunction "21_21") (pintype "passive"))
    )
    (net (code "59") (name "unconnected-(SV2-Pad22)") (class "Default")
      (node (ref "SV2") (pin "22") (pinfunction "22_22") (pintype "passive"))
    )
    (net (code "60") (name "unconnected-(SV2-Pad23)") (class "Default")
      (node (ref "SV2") (pin "23") (pinfunction "23_23") (pintype "passive"))
    )
    (net (code "61") (name "unconnected-(SV2-Pad24)") (class "Default")
      (node (ref "SV2") (pin "24") (pinfunction "24_24") (pintype "passive"))
    )
    (net (code "62") (name "unconnected-(U40-FLG-Pad3)") (class "Default")
      (node (ref "U40") (pin "3") (pinfunction "FLG_3") (pintype "bidirectional"))
    )
  )
)
